# Motor_Controller.net
KiCad netlist of a schematic drawn in Altium Designer
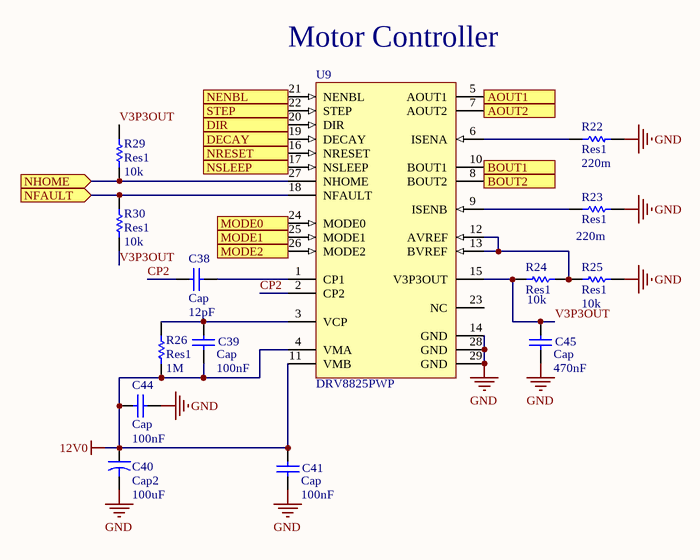
[diagram p0: Motor Controller.SchDoc]

(export (version "E")
  (design (tool "Eeschema 10.0.6"))
  (components
    (comp (ref "C38")
      (value "Cap")
      (footprint "0402-A")
      (description "Capacitor")
      (fields (field (name "ALTIUM_VALUE") "12pF") (field (name "PUBLISHER") "Altium Limited"))
      (libsource (lib "Miscellaneous Devices") (part "Cap"))
    )
    (comp (ref "C39")
      (value "Cap")
      (footprint "1608[0603]")
      (description "Capacitor")
      (fields (field (name "ALTIUM_VALUE") "100nF") (field (name "PUBLISHER") "Altium Limited"))
      (libsource (lib "Miscellaneous Devices") (part "Cap"))
    )
    (comp (ref "C40")
      (value "Cap2")
      (footprint "RAD-0.1")
      (description "Capacitor")
      (fields (field (name "ALTIUM_VALUE") "100uF") (field (name "PUBLISHER") "Altium Limited"))
      (libsource (lib "Miscellaneous Devices") (part "Cap2"))
    )
    (comp (ref "C41")
      (value "Cap")
      (footprint "1608[0603]")
      (description "Capacitor")
      (fields (field (name "ALTIUM_VALUE") "100nF") (field (name "PUBLISHER") "Altium Limited"))
      (libsource (lib "Miscellaneous Devices") (part "Cap"))
    )
    (comp (ref "C44")
      (value "Cap")
      (footprint "1608[0603]")
      (description "Capacitor")
      (fields (field (name "ALTIUM_VALUE") "100nF") (field (name "PUBLISHER") "Altium Limited"))
      (libsource (lib "Miscellaneous Devices") (part "Cap"))
    )
    (comp (ref "C45")
      (value "Cap")
      (footprint "1608[0603]")
      (description "Capacitor")
      (fields (field (name "ALTIUM_VALUE") "470nF") (field (name "PUBLISHER") "Altium Limited"))
      (libsource (lib "Miscellaneous Devices") (part "Cap"))
    )
    (comp (ref "R22")
      (value "Res1")
      (footprint "RC2512N_PAN")
      (description "Resistor")
      (fields (field (name "ALTIUM_VALUE") "220m") (field (name "PUBLISHER") "Altium Limited"))
      (libsource (lib "Miscellaneous Devices") (part "Res1"))
    )
    (comp (ref "R23")
      (value "Res1")
      (footprint "RC2512N_PAN")
      (description "Resistor")
      (fields (field (name "ALTIUM_VALUE") "220m") (field (name "PUBLISHER") "Altium Limited"))
      (libsource (lib "Miscellaneous Devices") (part "Res1"))
    )
    (comp (ref "R24")
      (value "Res1")
      (footprint "0402-A")
      (description "Resistor")
      (fields (field (name "ALTIUM_VALUE") "10k") (field (name "PUBLISHER") "Altium Limited"))
      (libsource (lib "Miscellaneous Devices") (part "Res1"))
    )
    (comp (ref "R25")
      (value "Res1")
      (footprint "0402-A")
      (description "Resistor")
      (fields (field (name "ALTIUM_VALUE") "10k") (field (name "PUBLISHER") "Altium Limited"))
      (libsource (lib "Miscellaneous Devices") (part "Res1"))
    )
    (comp (ref "R26")
      (value "Res1")
      (footprint "0402-A")
      (description "Resistor")
      (fields (field (name "ALTIUM_VALUE") "1M") (field (name "PUBLISHER") "Altium Limited"))
      (libsource (lib "Miscellaneous Devices") (part "Res1"))
    )
    (comp (ref "R29")
      (value "Res1")
      (footprint "0402-A")
      (description "Resistor")
      (fields (field (name "ALTIUM_VALUE") "10k") (field (name "PUBLISHER") "Altium Limited"))
      (libsource (lib "Miscellaneous Devices") (part "Res1"))
    )
    (comp (ref "R30")
      (value "Res1")
      (footprint "0402-A")
      (description "Resistor")
      (fields (field (name "ALTIUM_VALUE") "10k") (field (name "PUBLISHER") "Altium Limited"))
      (libsource (lib "Miscellaneous Devices") (part "Res1"))
    )
    (comp (ref "U9")
      (value "DRV8825PWP")
      (footprint "PWP0028C_L")
      (fields (field (name "TOLERANCE") "20%"))
      (libsource (lib "Altium Content Vault") (part "TI-DRV882XPWP28-XXXXXXXXXTP"))
    )
  )
  (nets
    (net (code "1") (name "/AOUT1") (class "Default")
      (node (ref "U9") (pin "5") (pinfunction "AOUT1_5") (pintype "tri_state"))
    )
    (net (code "2") (name "/AOUT2") (class "Default")
      (node (ref "U9") (pin "7") (pinfunction "AOUT2_7") (pintype "tri_state"))
    )
    (net (code "3") (name "/BOUT1") (class "Default")
      (node (ref "U9") (pin "10") (pinfunction "BOUT1_10") (pintype "tri_state"))
    )
    (net (code "4") (name "/BOUT2") (class "Default")
      (node (ref "U9") (pin "8") (pinfunction "BOUT2_8") (pintype "tri_state"))
    )
    (net (code "5") (name "/CP2") (class "Default")
      (node (ref "C38") (pin "2") (pinfunction "2_2") (pintype "passive"))
      (node (ref "U9") (pin "2") (pinfunction "CP2_2") (pintype "passive"))
    )
    (net (code "6") (name "/DECAY") (class "Default")
      (node (ref "U9") (pin "19") (pinfunction "DECAY_19") (pintype "input"))
    )
    (net (code "7") (name "/DIR") (class "Default")
      (node (ref "U9") (pin "20") (pinfunction "DIR_20") (pintype "input"))
    )
    (net (code "8") (name "/MODE0") (class "Default")
      (node (ref "U9") (pin "24") (pinfunction "MODE0_24") (pintype "input"))
    )
    (net (code "9") (name "/MODE1") (class "Default")
      (node (ref "U9") (pin "25") (pinfunction "MODE1_25") (pintype "input"))
    )
    (net (code "10") (name "/MODE2") (class "Default")
      (node (ref "U9") (pin "26") (pinfunction "MODE2_26") (pintype "input"))
    )
    (net (code "11") (name "/NENBL") (class "Default")
      (node (ref "U9") (pin "21") (pinfunction "NENBL_21") (pintype "input"))
    )
    (net (code "12") (name "/NFAULT") (class "Default")
      (node (ref "R30") (pin "2") (pinfunction "2_2") (pintype "passive"))
      (node (ref "U9") (pin "18") (pinfunction "NFAULT_18") (pintype "open_collector"))
    )
    (net (code "13") (name "/NHOME") (class "Default")
      (node (ref "R29") (pin "2") (pinfunction "2_2") (pintype "passive"))
      (node (ref "U9") (pin "27") (pinfunction "NHOME_27") (pintype "open_collector"))
    )
    (net (code "14") (name "/NRESET") (class "Default")
      (node (ref "U9") (pin "16") (pinfunction "NRESET_16") (pintype "input"))
    )
    (net (code "15") (name "/NSLEEP") (class "Default")
      (node (ref "U9") (pin "17") (pinfunction "NSLEEP_17") (pintype "input"))
    )
    (net (code "16") (name "/STEP") (class "Default")
      (node (ref "U9") (pin "22") (pinfunction "STEP_22") (pintype "input"))
    )
    (net (code "17") (name "/V3P3OUT") (class "Default")
      (node (ref "C45") (pin "2") (pinfunction "2_2") (pintype "passive"))
      (node (ref "R24") (pin "2") (pinfunction "2_2") (pintype "passive"))
      (node (ref "R29") (pin "1") (pinfunction "1_1") (pintype "passive"))
      (node (ref "R30") (pin "1") (pinfunction "1_1") (pintype "passive"))
      (node (ref "U9") (pin "15") (pinfunction "V3P3OUT_15") (pintype "power_in"))
    )
    (net (code "18") (name "12V0") (class "Default")
      (node (ref "C39") (pin "1") (pinfunction "1_1") (pintype "passive"))
      (node (ref "C40") (pin "1") (pinfunction "1_1") (pintype "passive"))
      (node (ref "C41") (pin "2") (pinfunction "2_2") (pintype "passive"))
      (node (ref "C44") (pin "2") (pinfunction "2_2") (pintype "passive"))
      (node (ref "R26") (pin "1") (pinfunction "1_1") (pintype "passive"))
      (node (ref "U9") (pin "11") (pinfunction "VMB_11") (pintype "power_in"))
      (node (ref "U9") (pin "4") (pinfunction "VMA_4") (pintype "power_in"))
    )
    (net (code "19") (name "GND") (class "Default")
      (node (ref "C40") (pin "2") (pinfunction "2_2") (pintype "passive"))
      (node (ref "C41") (pin "1") (pinfunction "1_1") (pintype "passive"))
      (node (ref "C44") (pin "1") (pinfunction "1_1") (pintype "passive"))
      (node (ref "C45") (pin "1") (pinfunction "1_1") (pintype "passive"))
      (node (ref "R22") (pin "1") (pinfunction "1_1") (pintype "passive"))
      (node (ref "R23") (pin "1") (pinfunction "1_1") (pintype "passive"))
      (node (ref "R25") (pin "2") (pinfunction "2_2") (pintype "passive"))
      (node (ref "U9") (pin "14") (pinfunction "GND_14") (pintype "power_in"))
      (node (ref "U9") (pin "28") (pinfunction "GND_28") (pintype "power_in"))
      (node (ref "U9") (pin "29") (pinfunction "GND_29") (pintype "power_in"))
    )
    (net (code "20") (name "Net-(U9-AVREF)") (class "Default")
      (node (ref "R24") (pin "1") (pinfunction "1_1") (pintype "passive"))
      (node (ref "R25") (pin "1") (pinfunction "1_1") (pintype "passive"))
      (node (ref "U9") (pin "12") (pinfunction "AVREF_12") (pintype "input"))
      (node (ref "U9") (pin "13") (pinfunction "BVREF_13") (pintype "input"))
    )
    (net (code "21") (name "Net-(U9-CP1)") (class "Default")
      (node (ref "C38") (pin "1") (pinfunction "1_1") (pintype "passive"))
      (node (ref "U9") (pin "1") (pinfunction "CP1_1") (pintype "passive"))
    )
    (net (code "22") (name "Net-(U9-ISENA)") (class "Default")
      (node (ref "R22") (pin "2") (pinfunction "2_2") (pintype "passive"))
      (node (ref "U9") (pin "6") (pinfunction "ISENA_6") (pintype "input"))
    )
    (net (code "23") (name "Net-(U9-ISENB)") (class "Default")
      (node (ref "R23") (pin "2") (pinfunction "2_2") (pintype "passive"))
      (node (ref "U9") (pin "9") (pinfunction "ISENB_9") (pintype "input"))
    )
    (net (code "24") (name "Net-(U9-VCP)") (class "Default")
      (node (ref "C39") (pin "2") (pinfunction "2_2") (pintype "passive"))
      (node (ref "R26") (pin "2") (pinfunction "2_2") (pintype "passive"))
      (node (ref "U9") (pin "3") (pinfunction "VCP_3") (pintype "passive"))
    )
    (net (code "25") (name "unconnected-(U9-NC-Pad23)") (class "Default")
      (node (ref "U9") (pin "23") (pinfunction "NC_23") (pintype "passive"))
    )
  )
)
